# LOOM_-_LV_BOX.net
KiCad netlist of a schematic drawn in Altium Designer
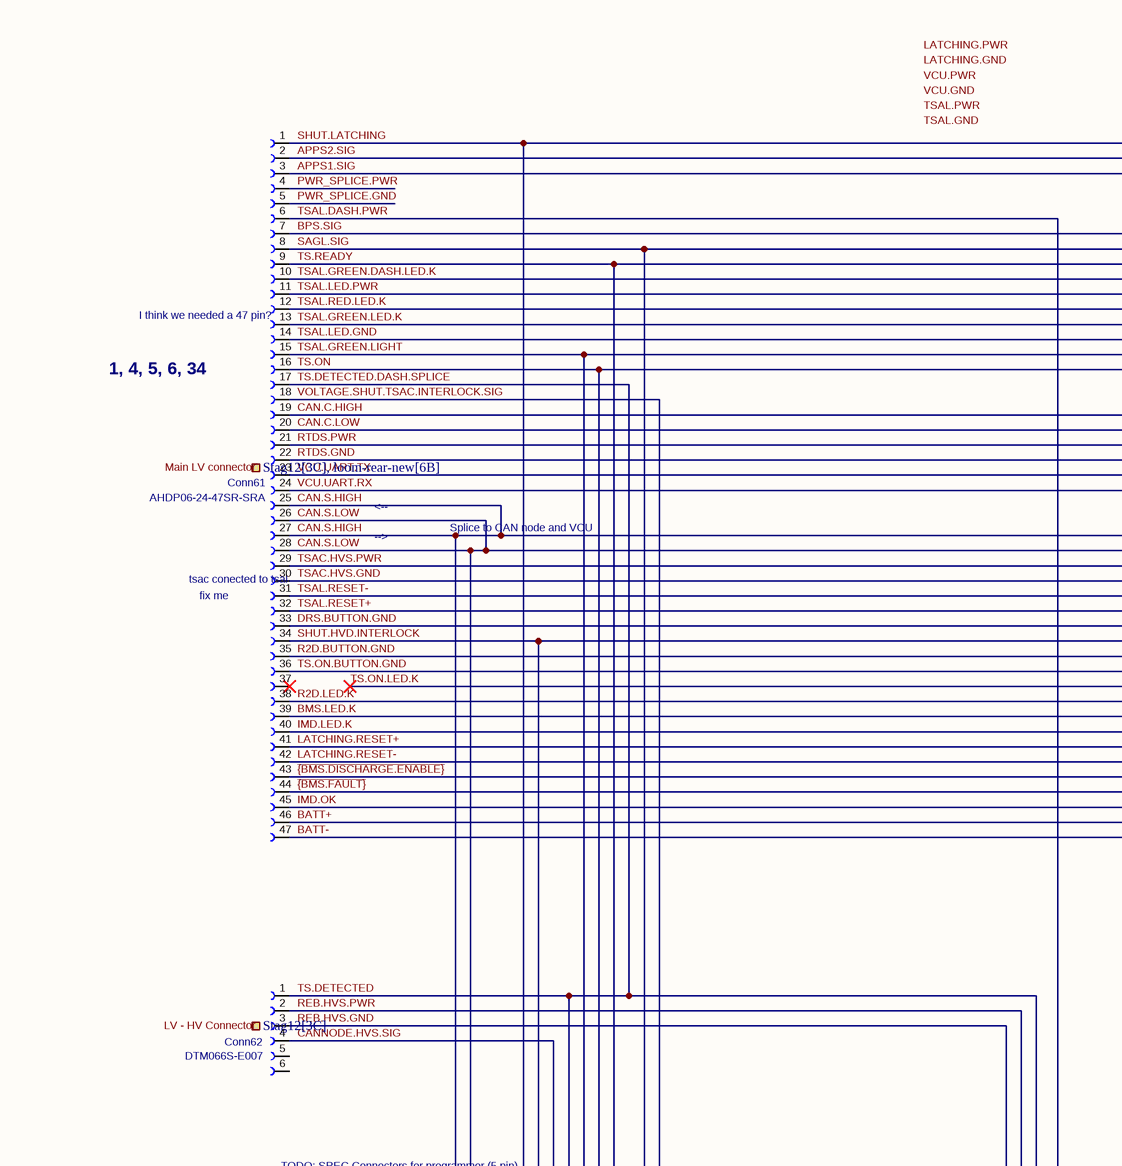
[diagram p0: LOOM - LV BOX.SchDoc, top left]
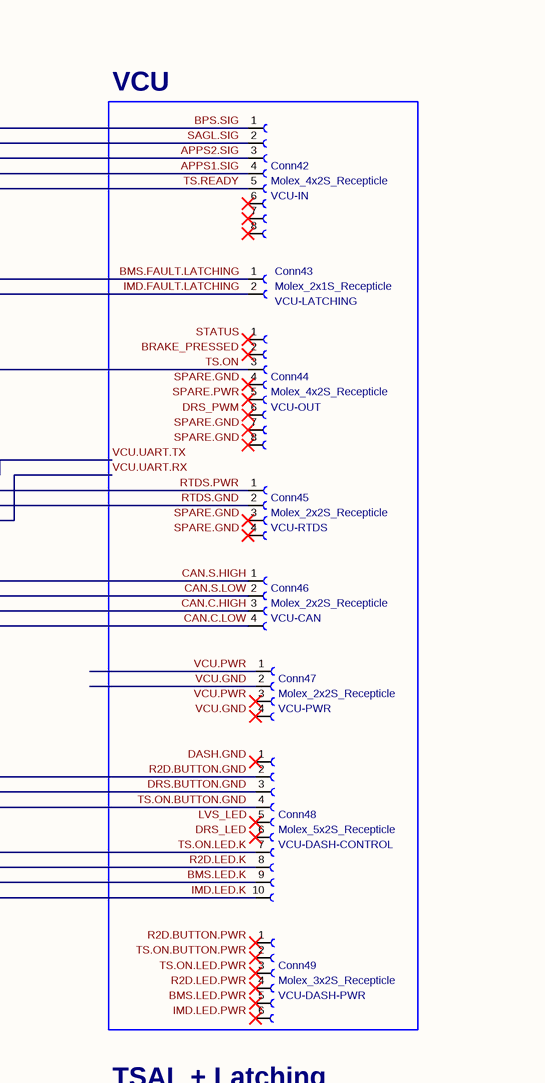
[diagram p1: LOOM - LV BOX.SchDoc, top right]
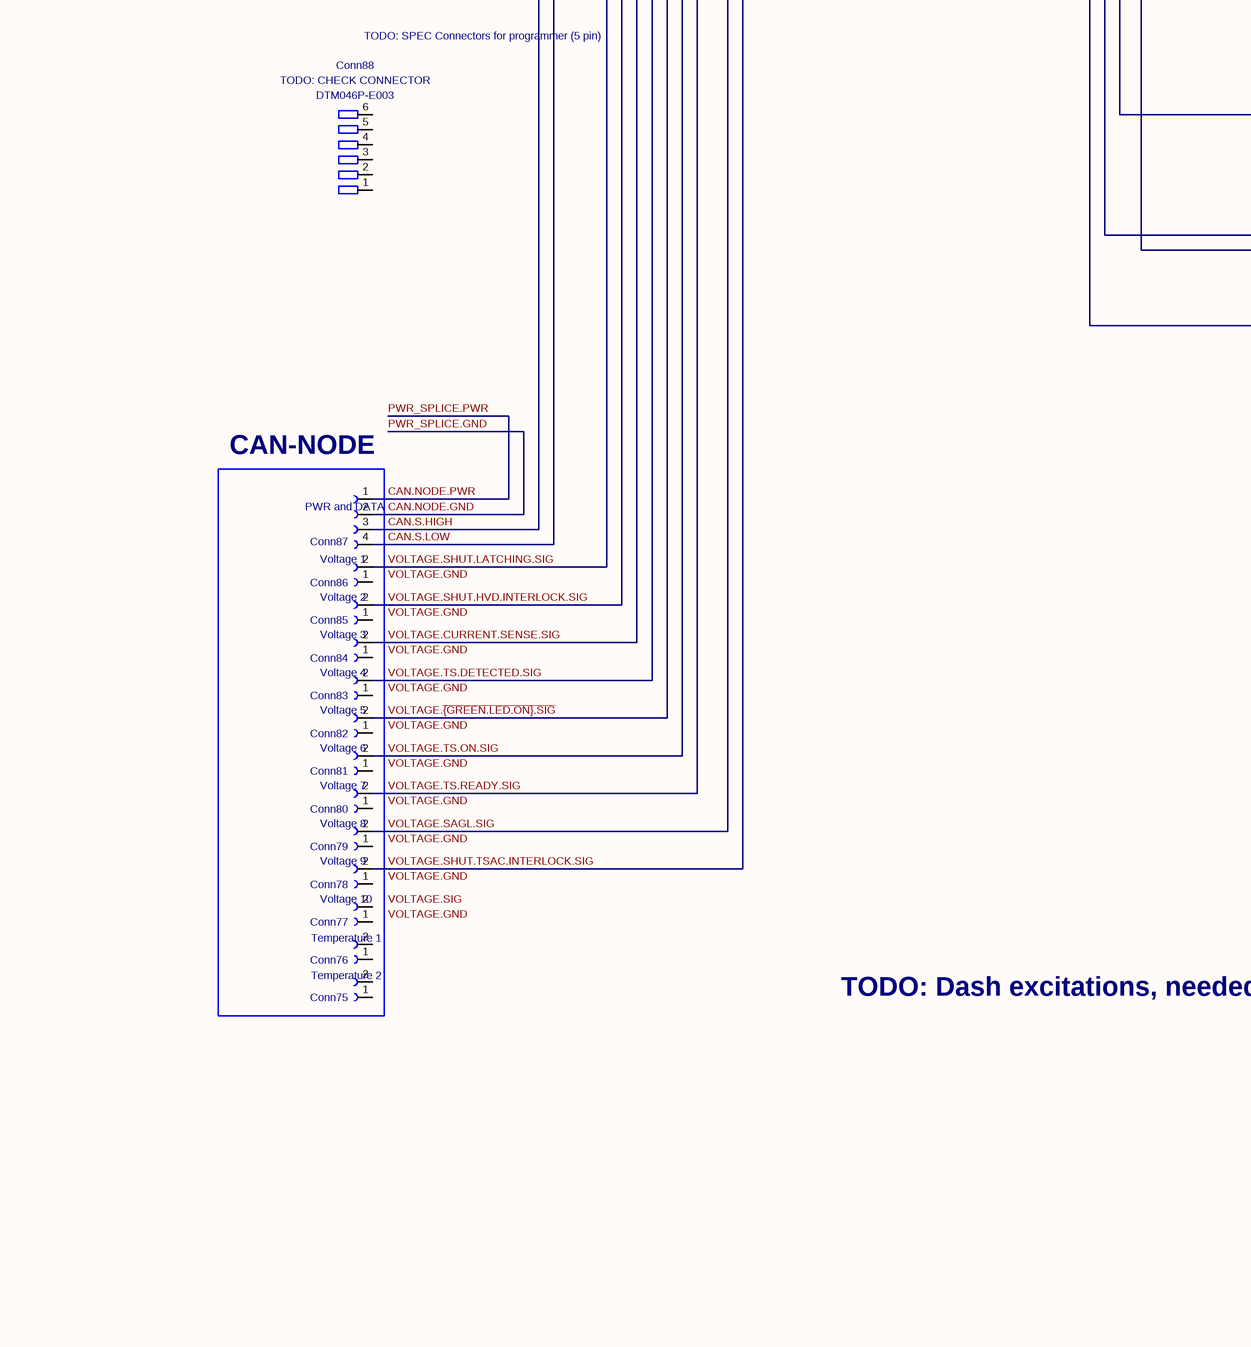
[diagram p2: LOOM - LV BOX.SchDoc, bottom left]
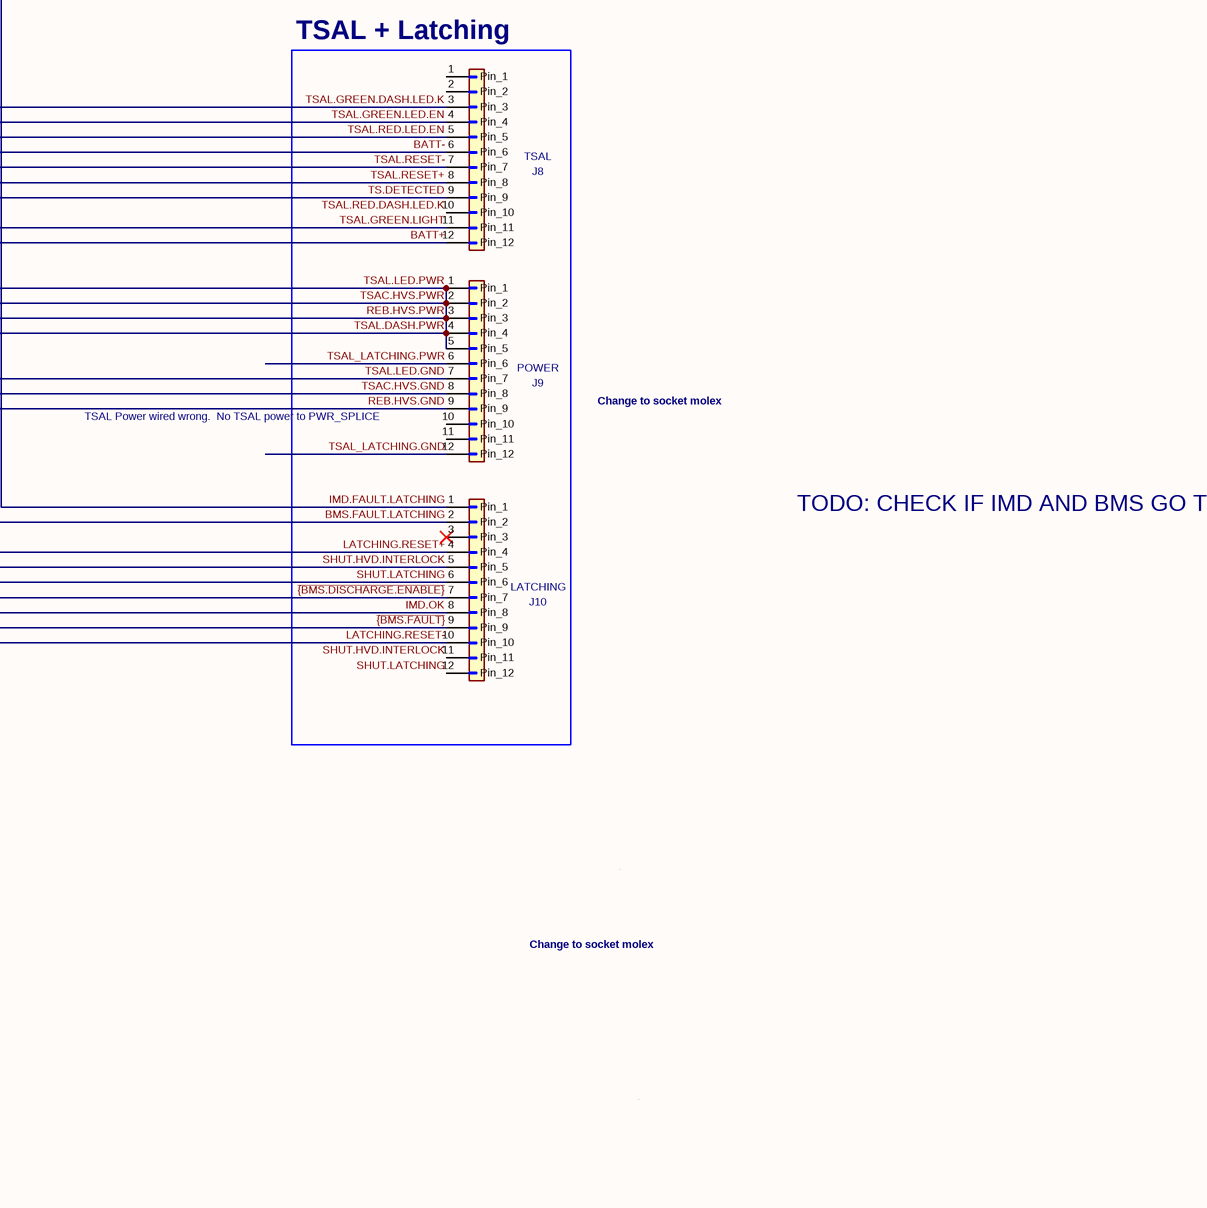
[diagram p3: LOOM - LV BOX.SchDoc, bottom right]

(export (version "E")
  (design (tool "Eeschema 10.0.6"))
  (components
    (comp (ref "Conn42")
      (value "Molex_4x2S_Recepticle")
      (fields (field (name "CONN NAME") "VCU-IN"))
      (libsource (lib "Connectors_SUFST") (part "Molex_4x2S_Recepticle"))
    )
    (comp (ref "Conn43")
      (value "Molex_2x1S_Recepticle")
      (fields (field (name "CONN NAME") "VCU-LATCHING"))
      (libsource (lib "Connectors_SUFST") (part "Molex_2x1S_Recepticle"))
    )
    (comp (ref "Conn44")
      (value "Molex_4x2S_Recepticle")
      (fields (field (name "CONN NAME") "VCU-OUT"))
      (libsource (lib "Connectors_SUFST") (part "Molex_4x2S_Recepticle"))
    )
    (comp (ref "Conn45")
      (value "Molex_2x2S_Recepticle")
      (fields (field (name "CONN NAME") "VCU-RTDS"))
      (libsource (lib "Connectors_SUFST") (part "Molex_2x2S_Recepticle"))
    )
    (comp (ref "Conn46")
      (value "Molex_2x2S_Recepticle")
      (fields (field (name "CONN NAME") "VCU-CAN"))
      (libsource (lib "Connectors_SUFST") (part "Molex_2x2S_Recepticle"))
    )
    (comp (ref "Conn47")
      (value "Molex_2x2S_Recepticle")
      (fields (field (name "CONN NAME") "VCU-PWR"))
      (libsource (lib "Connectors_SUFST") (part "Molex_2x2S_Recepticle"))
    )
    (comp (ref "Conn48")
      (value "Molex_5x2S_Recepticle")
      (fields (field (name "CONN NAME") "VCU-DASH-CONTROL"))
      (libsource (lib "Connectors_SUFST") (part "Molex_5x2S_Recepticle"))
    )
    (comp (ref "Conn49")
      (value "Molex_3x2S_Recepticle")
      (fields (field (name "CONN NAME") "VCU-DASH-PWR"))
      (libsource (lib "Connectors_SUFST") (part "Molex_3x2S_Recepticle"))
    )
    (comp (ref "Conn61")
      (value "AMPHENOL-47P-Recepticle")
      (fields (field (name "P/N") "AHDP06-24-47SR-SRA"))
      (libsource (lib "Connectors_SUFST") (part "AMPHENOL-47P-Recepticle"))
    )
    (comp (ref "Conn62")
      (value "Deutsch_DTM_12S_Pin")
      (fields (field (name "P/N") "DTM066S-E007"))
      (libsource (lib "Connectors_SUFST") (part "Deutsch_DTM_6S_Pin"))
    )
    (comp (ref "Conn75")
      (value "Molex_2x1S_Recepticle")
      (libsource (lib "Connectors_SUFST") (part "Molex_2x1S_Recepticle"))
    )
    (comp (ref "Conn76")
      (value "Molex_2x1S_Recepticle")
      (libsource (lib "Connectors_SUFST") (part "Molex_2x1S_Recepticle"))
    )
    (comp (ref "Conn77")
      (value "Molex_2x1S_Recepticle")
      (libsource (lib "Connectors_SUFST") (part "Molex_2x1S_Recepticle"))
    )
    (comp (ref "Conn78")
      (value "Molex_2x1S_Recepticle")
      (libsource (lib "Connectors_SUFST") (part "Molex_2x1S_Recepticle"))
    )
    (comp (ref "Conn79")
      (value "Molex_2x1S_Recepticle")
      (libsource (lib "Connectors_SUFST") (part "Molex_2x1S_Recepticle"))
    )
    (comp (ref "Conn80")
      (value "Molex_2x1S_Recepticle")
      (libsource (lib "Connectors_SUFST") (part "Molex_2x1S_Recepticle"))
    )
    (comp (ref "Conn81")
      (value "Molex_2x1S_Recepticle")
      (libsource (lib "Connectors_SUFST") (part "Molex_2x1S_Recepticle"))
    )
    (comp (ref "Conn82")
      (value "Molex_2x1S_Recepticle")
      (libsource (lib "Connectors_SUFST") (part "Molex_2x1S_Recepticle"))
    )
    (comp (ref "Conn83")
      (value "Molex_2x1S_Recepticle")
      (libsource (lib "Connectors_SUFST") (part "Molex_2x1S_Recepticle"))
    )
    (comp (ref "Conn84")
      (value "Molex_2x1S_Recepticle")
      (libsource (lib "Connectors_SUFST") (part "Molex_2x1S_Recepticle"))
    )
    (comp (ref "Conn85")
      (value "Molex_2x1S_Recepticle")
      (libsource (lib "Connectors_SUFST") (part "Molex_2x1S_Recepticle"))
    )
    (comp (ref "Conn86")
      (value "Molex_2x1S_Recepticle")
      (libsource (lib "Connectors_SUFST") (part "Molex_2x1S_Recepticle"))
    )
    (comp (ref "Conn87")
      (value "Molex_4x1S_Recepticle")
      (libsource (lib "Connectors_SUFST") (part "Molex_4x1S_Recepticle"))
    )
    (comp (ref "Conn88")
      (value "TODO: CHECK CONNECTOR")
      (fields (field (name "P/N") "DTM046P-E003"))
      (libsource (lib "Connectors_SUFST") (part "Deutsch_DTM_6P_Pin"))
    )
    (comp (ref "J8")
      (value "TSAL")
      (footprint "Molex_Micro-Fit_3.0_43045-1200_2x06_P3.00mm_Horizontal")
      (libsource (lib "Connector_Generic") (part "Conn_01x12"))
    )
    (comp (ref "J9")
      (value "POWER")
      (footprint "Molex_Micro-Fit_3.0_43045-1200_2x06_P3.00mm_Horizontal")
      (libsource (lib "Connector_Generic") (part "Conn_01x12"))
    )
    (comp (ref "J10")
      (value "LATCHING")
      (footprint "Molex_Micro-Fit_3.0_43045-1200_2x06_P3.00mm_Horizontal")
      (libsource (lib "Connector_Generic") (part "Conn_01x12"))
    )
  )
  (nets
    (net (code "1") (name "/APPS1.SIG") (class "Default")
      (node (ref "Conn42") (pin "4") (pinfunction "4_4") (pintype "passive"))
      (node (ref "Conn61") (pin "3") (pinfunction "3_3") (pintype "passive"))
    )
    (net (code "2") (name "/APPS2.SIG") (class "Default")
      (node (ref "Conn42") (pin "3") (pinfunction "3_3") (pintype "passive"))
      (node (ref "Conn61") (pin "2") (pinfunction "2_2") (pintype "passive"))
    )
    (net (code "3") (name "/BATT+") (class "Default")
      (node (ref "Conn61") (pin "46") (pinfunction "46_46") (pintype "passive"))
      (node (ref "J8") (pin "12") (pinfunction "Pin_12_12") (pintype "passive"))
    )
    (net (code "4") (name "/BATT-") (class "Default")
      (node (ref "Conn61") (pin "47") (pinfunction "47_47") (pintype "passive"))
      (node (ref "J8") (pin "6") (pinfunction "Pin_6_6") (pintype "passive"))
    )
    (net (code "5") (name "/BMS.FAULT.LATCHING") (class "Default")
      (node (ref "Conn43") (pin "1") (pinfunction "1_1") (pintype "passive"))
      (node (ref "J10") (pin "2") (pinfunction "Pin_2_2") (pintype "passive"))
    )
    (net (code "6") (name "/BMS.LED.K") (class "Default")
      (node (ref "Conn48") (pin "9") (pinfunction "9_9") (pintype "passive"))
      (node (ref "Conn61") (pin "39") (pinfunction "39_39") (pintype "passive"))
    )
    (net (code "8") (name "/BPS.SIG") (class "Default")
      (node (ref "Conn42") (pin "1") (pinfunction "1_1") (pintype "passive"))
      (node (ref "Conn61") (pin "7") (pinfunction "7_7") (pintype "passive"))
    )
    (net (code "10") (name "/CAN.C.HIGH") (class "Default")
      (node (ref "Conn46") (pin "3") (pinfunction "3_3") (pintype "passive"))
      (node (ref "Conn61") (pin "19") (pinfunction "19_19") (pintype "passive"))
    )
    (net (code "11") (name "/CAN.C.LOW") (class "Default")
      (node (ref "Conn46") (pin "4") (pinfunction "4_4") (pintype "passive"))
      (node (ref "Conn61") (pin "20") (pinfunction "20_20") (pintype "passive"))
    )
    (net (code "12") (name "/CAN.NODE.GND") (class "Default")
      (node (ref "Conn61") (pin "5") (pinfunction "5_5") (pintype "passive"))
      (node (ref "Conn87") (pin "2") (pinfunction "2_2") (pintype "passive"))
    )
    (net (code "13") (name "/CAN.NODE.PWR") (class "Default")
      (node (ref "Conn61") (pin "4") (pinfunction "4_4") (pintype "passive"))
      (node (ref "Conn87") (pin "1") (pinfunction "1_1") (pintype "passive"))
    )
    (net (code "14") (name "/CAN.S.HIGH") (class "Default")
      (node (ref "Conn46") (pin "1") (pinfunction "1_1") (pintype "passive"))
      (node (ref "Conn61") (pin "25") (pinfunction "25_25") (pintype "passive"))
      (node (ref "Conn61") (pin "27") (pinfunction "27_27") (pintype "passive"))
      (node (ref "Conn87") (pin "3") (pinfunction "3_3") (pintype "passive"))
    )
    (net (code "15") (name "/CAN.S.LOW") (class "Default")
      (node (ref "Conn46") (pin "2") (pinfunction "2_2") (pintype "passive"))
      (node (ref "Conn61") (pin "26") (pinfunction "26_26") (pintype "passive"))
      (node (ref "Conn61") (pin "28") (pinfunction "28_28") (pintype "passive"))
      (node (ref "Conn87") (pin "4") (pinfunction "4_4") (pintype "passive"))
    )
    (net (code "16") (name "/CANNODE.HVS.SIG") (class "Default")
      (node (ref "Conn62") (pin "4") (pinfunction "4_4") (pintype "passive"))
      (node (ref "Conn84") (pin "2") (pinfunction "2_2") (pintype "passive"))
    )
    (net (code "18") (name "/DRS.BUTTON.GND") (class "Default")
      (node (ref "Conn48") (pin "3") (pinfunction "3_3") (pintype "passive"))
      (node (ref "Conn61") (pin "33") (pinfunction "33_33") (pintype "passive"))
    )
    (net (code "21") (name "/IMD.FAULT.LATCHING") (class "Default")
      (node (ref "Conn43") (pin "2") (pinfunction "2_2") (pintype "passive"))
      (node (ref "J10") (pin "1") (pinfunction "Pin_1_1") (pintype "passive"))
    )
    (net (code "22") (name "/IMD.LED.K") (class "Default")
      (node (ref "Conn48") (pin "10") (pinfunction "10_10") (pintype "passive"))
      (node (ref "Conn61") (pin "40") (pinfunction "40_40") (pintype "passive"))
    )
    (net (code "24") (name "/IMD.OK") (class "Default")
      (node (ref "Conn61") (pin "45") (pinfunction "45_45") (pintype "passive"))
      (node (ref "J10") (pin "8") (pinfunction "Pin_8_8") (pintype "passive"))
    )
    (net (code "27") (name "/LATCHING.RESET+") (class "Default")
      (node (ref "Conn61") (pin "41") (pinfunction "41_41") (pintype "passive"))
      (node (ref "J10") (pin "4") (pinfunction "Pin_4_4") (pintype "passive"))
    )
    (net (code "28") (name "/LATCHING.RESET-") (class "Default")
      (node (ref "Conn61") (pin "42") (pinfunction "42_42") (pintype "passive"))
      (node (ref "J10") (pin "10") (pinfunction "Pin_10_10") (pintype "passive"))
    )
    (net (code "32") (name "/R2D.BUTTON.GND") (class "Default")
      (node (ref "Conn48") (pin "2") (pinfunction "2_2") (pintype "passive"))
      (node (ref "Conn61") (pin "35") (pinfunction "35_35") (pintype "passive"))
    )
    (net (code "34") (name "/R2D.LED.K") (class "Default")
      (node (ref "Conn48") (pin "8") (pinfunction "8_8") (pintype "passive"))
      (node (ref "Conn61") (pin "38") (pinfunction "38_38") (pintype "passive"))
    )
    (net (code "36") (name "/REB.HVS.GND") (class "Default")
      (node (ref "Conn62") (pin "3") (pinfunction "3_3") (pintype "passive"))
      (node (ref "J9") (pin "9") (pinfunction "Pin_9_9") (pintype "passive"))
    )
    (net (code "37") (name "/REB.HVS.PWR") (class "Default")
      (node (ref "Conn61") (pin "11") (pinfunction "11_11") (pintype "passive"))
      (node (ref "Conn61") (pin "29") (pinfunction "29_29") (pintype "passive"))
      (node (ref "Conn61") (pin "6") (pinfunction "6_6") (pintype "passive"))
      (node (ref "Conn62") (pin "2") (pinfunction "2_2") (pintype "passive"))
      (node (ref "J9") (pin "1") (pinfunction "Pin_1_1") (pintype "passive"))
      (node (ref "J9") (pin "2") (pinfunction "Pin_2_2") (pintype "passive"))
      (node (ref "J9") (pin "3") (pinfunction "Pin_3_3") (pintype "passive"))
      (node (ref "J9") (pin "4") (pinfunction "Pin_4_4") (pintype "passive"))
      (node (ref "J9") (pin "5") (pinfunction "Pin_5_5") (pintype "passive"))
    )
    (net (code "38") (name "/RTDS.GND") (class "Default")
      (node (ref "Conn45") (pin "2") (pinfunction "2_2") (pintype "passive"))
      (node (ref "Conn61") (pin "22") (pinfunction "22_22") (pintype "passive"))
    )
    (net (code "39") (name "/RTDS.PWR") (class "Default")
      (node (ref "Conn45") (pin "1") (pinfunction "1_1") (pintype "passive"))
      (node (ref "Conn61") (pin "21") (pinfunction "21_21") (pintype "passive"))
    )
    (net (code "40") (name "/SAGL.SIG") (class "Default")
      (node (ref "Conn42") (pin "2") (pinfunction "2_2") (pintype "passive"))
      (node (ref "Conn61") (pin "8") (pinfunction "8_8") (pintype "passive"))
      (node (ref "Conn79") (pin "2") (pinfunction "2_2") (pintype "passive"))
    )
    (net (code "41") (name "/SHUT.HVD.INTERLOCK") (class "Default")
      (node (ref "Conn61") (pin "34") (pinfunction "34_34") (pintype "passive"))
      (node (ref "Conn85") (pin "2") (pinfunction "2_2") (pintype "passive"))
      (node (ref "J10") (pin "11") (pinfunction "Pin_11_11") (pintype "passive"))
      (node (ref "J10") (pin "5") (pinfunction "Pin_5_5") (pintype "passive"))
    )
    (net (code "42") (name "/SHUT.LATCHING") (class "Default")
      (node (ref "Conn61") (pin "1") (pinfunction "1_1") (pintype "passive"))
      (node (ref "Conn86") (pin "2") (pinfunction "2_2") (pintype "passive"))
      (node (ref "J10") (pin "12") (pinfunction "Pin_12_12") (pintype "passive"))
      (node (ref "J10") (pin "6") (pinfunction "Pin_6_6") (pintype "passive"))
    )
    (net (code "46") (name "/TS.DETECTED") (class "Default")
      (node (ref "Conn61") (pin "17") (pinfunction "17_17") (pintype "passive"))
      (node (ref "Conn62") (pin "1") (pinfunction "1_1") (pintype "passive"))
      (node (ref "Conn83") (pin "2") (pinfunction "2_2") (pintype "passive"))
      (node (ref "J8") (pin "9") (pinfunction "Pin_9_9") (pintype "passive"))
    )
    (net (code "47") (name "/TS.ON") (class "Default")
      (node (ref "Conn44") (pin "3") (pinfunction "3_3") (pintype "passive"))
      (node (ref "Conn61") (pin "16") (pinfunction "16_16") (pintype "passive"))
      (node (ref "Conn81") (pin "2") (pinfunction "2_2") (pintype "passive"))
    )
    (net (code "48") (name "/TS.ON.BUTTON.GND") (class "Default")
      (node (ref "Conn48") (pin "4") (pinfunction "4_4") (pintype "passive"))
      (node (ref "Conn61") (pin "36") (pinfunction "36_36") (pintype "passive"))
    )
    (net (code "50") (name "/TS.ON.LED.K") (class "Default")
      (node (ref "Conn48") (pin "7") (pinfunction "7_7") (pintype "passive+no_connect"))
    )
    (net (code "52") (name "/TS.READY") (class "Default")
      (node (ref "Conn42") (pin "5") (pinfunction "5_5") (pintype "passive"))
      (node (ref "Conn61") (pin "9") (pinfunction "9_9") (pintype "passive"))
      (node (ref "Conn80") (pin "2") (pinfunction "2_2") (pintype "passive"))
    )
    (net (code "53") (name "/TSAC.HVS.GND") (class "Default")
      (node (ref "Conn61") (pin "30") (pinfunction "30_30") (pintype "passive"))
      (node (ref "J9") (pin "8") (pinfunction "Pin_8_8") (pintype "passive"))
    )
    (net (code "55") (name "/TSAL.GREEN.DASH.LED.K") (class "Default")
      (node (ref "Conn61") (pin "10") (pinfunction "10_10") (pintype "passive"))
      (node (ref "J8") (pin "3") (pinfunction "Pin_3_3") (pintype "passive"))
    )
    (net (code "56") (name "/TSAL.GREEN.LED.EN") (class "Default")
      (node (ref "Conn61") (pin "13") (pinfunction "13_13") (pintype "passive"))
      (node (ref "J8") (pin "4") (pinfunction "Pin_4_4") (pintype "passive"))
    )
    (net (code "57") (name "/TSAL.GREEN.LIGHT") (class "Default")
      (node (ref "Conn61") (pin "15") (pinfunction "15_15") (pintype "passive"))
      (node (ref "Conn82") (pin "2") (pinfunction "2_2") (pintype "passive"))
      (node (ref "J8") (pin "11") (pinfunction "Pin_11_11") (pintype "passive"))
    )
    (net (code "58") (name "/TSAL.LED.GND") (class "Default")
      (node (ref "Conn61") (pin "14") (pinfunction "14_14") (pintype "passive"))
      (node (ref "J9") (pin "7") (pinfunction "Pin_7_7") (pintype "passive"))
    )
    (net (code "60") (name "/TSAL.RED.DASH.LED.K") (class "Default")
      (node (ref "J8") (pin "10") (pinfunction "Pin_10_10") (pintype "passive"))
    )
    (net (code "61") (name "/TSAL.RED.LED.EN") (class "Default")
      (node (ref "Conn61") (pin "12") (pinfunction "12_12") (pintype "passive"))
      (node (ref "J8") (pin "5") (pinfunction "Pin_5_5") (pintype "passive"))
    )
    (net (code "62") (name "/TSAL.RESET+") (class "Default")
      (node (ref "Conn61") (pin "32") (pinfunction "32_32") (pintype "passive"))
      (node (ref "J8") (pin "8") (pinfunction "Pin_8_8") (pintype "passive"))
    )
    (net (code "63") (name "/TSAL.RESET-") (class "Default")
      (node (ref "Conn61") (pin "31") (pinfunction "31_31") (pintype "passive"))
      (node (ref "J8") (pin "7") (pinfunction "Pin_7_7") (pintype "passive"))
    )
    (net (code "64") (name "/TSAL_LATCHING.GND") (class "Default")
      (node (ref "J9") (pin "12") (pinfunction "Pin_12_12") (pintype "passive"))
    )
    (net (code "65") (name "/TSAL_LATCHING.PWR") (class "Default")
      (node (ref "J9") (pin "6") (pinfunction "Pin_6_6") (pintype "passive"))
    )
    (net (code "66") (name "/VCU.GND") (class "Default")
      (node (ref "Conn47") (pin "2") (pinfunction "2_2") (pintype "passive"))
    )
    (net (code "67") (name "/VCU.PWR") (class "Default")
      (node (ref "Conn47") (pin "1") (pinfunction "1_1") (pintype "passive"))
    )
    (net (code "68") (name "/VCU.UART.RX") (class "Default")
      (node (ref "Conn61") (pin "24") (pinfunction "24_24") (pintype "passive"))
    )
    (net (code "69") (name "/VCU.UART.TX") (class "Default")
      (node (ref "Conn61") (pin "23") (pinfunction "23_23") (pintype "passive"))
    )
    (net (code "71") (name "/VOLTAGE.SHUT.TSAC.INTERLOCK.SIG") (class "Default")
      (node (ref "Conn61") (pin "18") (pinfunction "18_18") (pintype "passive"))
      (node (ref "Conn78") (pin "2") (pinfunction "2_2") (pintype "passive"))
    )
    (net (code "73") (name "/~{{BMS.DISCHARGE.ENABLE}}") (class "Default")
      (node (ref "Conn61") (pin "43") (pinfunction "43_43") (pintype "passive"))
      (node (ref "J10") (pin "7") (pinfunction "Pin_7_7") (pintype "passive"))
    )
    (net (code "74") (name "/~{{BMS.FAULT}}") (class "Default")
      (node (ref "Conn61") (pin "44") (pinfunction "44_44") (pintype "passive"))
      (node (ref "J10") (pin "9") (pinfunction "Pin_9_9") (pintype "passive"))
    )
    (net (code "75") (name "unconnected-(Conn42-Pad6)") (class "Default")
      (node (ref "Conn42") (pin "6") (pinfunction "6_6") (pintype "passive+no_connect"))
    )
    (net (code "76") (name "unconnected-(Conn42-Pad7)") (class "Default")
      (node (ref "Conn42") (pin "7") (pinfunction "7_7") (pintype "passive+no_connect"))
    )
    (net (code "77") (name "unconnected-(Conn42-Pad8)") (class "Default")
      (node (ref "Conn42") (pin "8") (pinfunction "8_8") (pintype "passive+no_connect"))
    )
    (net (code "78") (name "unconnected-(Conn44-Pad1)") (class "Default")
      (node (ref "Conn44") (pin "1") (pinfunction "1_1") (pintype "passive+no_connect"))
    )
    (net (code "79") (name "unconnected-(Conn44-Pad2)") (class "Default")
      (node (ref "Conn44") (pin "2") (pinfunction "2_2") (pintype "passive+no_connect"))
    )
    (net (code "80") (name "unconnected-(Conn44-Pad4)") (class "Default")
      (node (ref "Conn44") (pin "4") (pinfunction "4_4") (pintype "passive+no_connect"))
    )
    (net (code "81") (name "unconnected-(Conn44-Pad5)") (class "Default")
      (node (ref "Conn44") (pin "5") (pinfunction "5_5") (pintype "passive+no_connect"))
    )
    (net (code "82") (name "unconnected-(Conn44-Pad6)") (class "Default")
      (node (ref "Conn44") (pin "6") (pinfunction "6_6") (pintype "passive+no_connect"))
    )
    (net (code "83") (name "unconnected-(Conn44-Pad7)") (class "Default")
      (node (ref "Conn44") (pin "7") (pinfunction "7_7") (pintype "passive+no_connect"))
    )
    (net (code "84") (name "unconnected-(Conn44-Pad8)") (class "Default")
      (node (ref "Conn44") (pin "8") (pinfunction "8_8") (pintype "passive+no_connect"))
    )
    (net (code "85") (name "unconnected-(Conn45-Pad3)") (class "Default")
      (node (ref "Conn45") (pin "3") (pinfunction "3_3") (pintype "passive+no_connect"))
    )
    (net (code "86") (name "unconnected-(Conn45-Pad4)") (class "Default")
      (node (ref "Conn45") (pin "4") (pinfunction "4_4") (pintype "passive+no_connect"))
    )
    (net (code "87") (name "unconnected-(Conn47-Pad3)") (class "Default")
      (node (ref "Conn47") (pin "3") (pinfunction "3_3") (pintype "passive+no_connect"))
    )
    (net (code "88") (name "unconnected-(Conn47-Pad4)") (class "Default")
      (node (ref "Conn47") (pin "4") (pinfunction "4_4") (pintype "passive+no_connect"))
    )
    (net (code "89") (name "unconnected-(Conn48-Pad1)") (class "Default")
      (node (ref "Conn48") (pin "1") (pinfunction "1_1") (pintype "passive+no_connect"))
    )
    (net (code "90") (name "unconnected-(Conn48-Pad5)") (class "Default")
      (node (ref "Conn48") (pin "5") (pinfunction "5_5") (pintype "passive+no_connect"))
    )
    (net (code "91") (name "unconnected-(Conn48-Pad6)") (class "Default")
      (node (ref "Conn48") (pin "6") (pinfunction "6_6") (pintype "passive+no_connect"))
    )
    (net (code "92") (name "unconnected-(Conn49-Pad1)") (class "Default")
      (node (ref "Conn49") (pin "1") (pinfunction "1_1") (pintype "passive+no_connect"))
    )
    (net (code "93") (name "unconnected-(Conn49-Pad2)") (class "Default")
      (node (ref "Conn49") (pin "2") (pinfunction "2_2") (pintype "passive+no_connect"))
    )
    (net (code "94") (name "unconnected-(Conn49-Pad3)") (class "Default")
      (node (ref "Conn49") (pin "3") (pinfunction "3_3") (pintype "passive+no_connect"))
    )
    (net (code "95") (name "unconnected-(Conn49-Pad4)") (class "Default")
      (node (ref "Conn49") (pin "4") (pinfunction "4_4") (pintype "passive+no_connect"))
    )
    (net (code "96") (name "unconnected-(Conn49-Pad5)") (class "Default")
      (node (ref "Conn49") (pin "5") (pinfunction "5_5") (pintype "passive+no_connect"))
    )
    (net (code "97") (name "unconnected-(Conn49-Pad6)") (class "Default")
      (node (ref "Conn49") (pin "6") (pinfunction "6_6") (pintype "passive+no_connect"))
    )
    (net (code "98") (name "unconnected-(Conn61-Pad37)") (class "Default")
      (node (ref "Conn61") (pin "37") (pinfunction "37_37") (pintype "passive+no_connect"))
    )
    (net (code "99") (name "unconnected-(Conn62-Pad5)") (class "Default")
      (node (ref "Conn62") (pin "5") (pinfunction "5_5") (pintype "passive"))
    )
    (net (code "100") (name "unconnected-(Conn62-Pad6)") (class "Default")
      (node (ref "Conn62") (pin "6") (pinfunction "6_6") (pintype "passive"))
    )
    (net (code "101") (name "unconnected-(Conn75-Pad1)") (class "Default")
      (node (ref "Conn75") (pin "1") (pinfunction "1_1") (pintype "passive"))
    )
    (net (code "102") (name "unconnected-(Conn75-Pad2)") (class "Default")
      (node (ref "Conn75") (pin "2") (pinfunction "2_2") (pintype "passive"))
    )
    (net (code "103") (name "unconnected-(Conn76-Pad1)") (class "Default")
      (node (ref "Conn76") (pin "1") (pinfunction "1_1") (pintype "passive"))
    )
    (net (code "104") (name "unconnected-(Conn76-Pad2)") (class "Default")
      (node (ref "Conn76") (pin "2") (pinfunction "2_2") (pintype "passive"))
    )
    (net (code "105") (name "unconnected-(Conn77-Pad1)") (class "Default")
      (node (ref "Conn77") (pin "1") (pinfunction "1_1") (pintype "passive"))
    )
    (net (code "106") (name "unconnected-(Conn77-Pad2)") (class "Default")
      (node (ref "Conn77") (pin "2") (pinfunction "2_2") (pintype "passive"))
    )
    (net (code "107") (name "unconnected-(Conn78-Pad1)") (class "Default")
      (node (ref "Conn78") (pin "1") (pinfunction "1_1") (pintype "passive"))
    )
    (net (code "108") (name "unconnected-(Conn79-Pad1)") (class "Default")
      (node (ref "Conn79") (pin "1") (pinfunction "1_1") (pintype "passive"))
    )
    (net (code "109") (name "unconnected-(Conn80-Pad1)") (class "Default")
      (node (ref "Conn80") (pin "1") (pinfunction "1_1") (pintype "passive"))
    )
    (net (code "110") (name "unconnected-(Conn81-Pad1)") (class "Default")
      (node (ref "Conn81") (pin "1") (pinfunction "1_1") (pintype "passive"))
    )
    (net (code "111") (name "unconnected-(Conn82-Pad1)") (class "Default")
      (node (ref "Conn82") (pin "1") (pinfunction "1_1") (pintype "passive"))
    )
    (net (code "112") (name "unconnected-(Conn83-Pad1)") (class "Default")
      (node (ref "Conn83") (pin "1") (pinfunction "1_1") (pintype "passive"))
    )
    (net (code "113") (name "unconnected-(Conn84-Pad1)") (class "Default")
      (node (ref "Conn84") (pin "1") (pinfunction "1_1") (pintype "passive"))
    )
    (net (code "114") (name "unconnected-(Conn85-Pad1)") (class "Default")
      (node (ref "Conn85") (pin "1") (pinfunction "1_1") (pintype "passive"))
    )
    (net (code "115") (name "unconnected-(Conn86-Pad1)") (class "Default")
      (node (ref "Conn86") (pin "1") (pinfunction "1_1") (pintype "passive"))
    )
    (net (code "116") (name "unconnected-(Conn88-Pad1)") (class "Default")
      (node (ref "Conn88") (pin "1") (pinfunction "1_1") (pintype "passive"))
    )
    (net (code "117") (name "unconnected-(Conn88-Pad2)") (class "Default")
      (node (ref "Conn88") (pin "2") (pinfunction "2_2") (pintype "passive"))
    )
    (net (code "118") (name "unconnected-(Conn88-Pad3)") (class "Default")
      (node (ref "Conn88") (pin "3") (pinfunction "3_3") (pintype "passive"))
    )
    (net (code "119") (name "unconnected-(Conn88-Pad4)") (class "Default")
      (node (ref "Conn88") (pin "4") (pinfunction "4_4") (pintype "passive"))
    )
    (net (code "120") (name "unconnected-(Conn88-Pad5)") (class "Default")
      (node (ref "Conn88") (pin "5") (pinfunction "5_5") (pintype "passive"))
    )
    (net (code "121") (name "unconnected-(Conn88-Pad6)") (class "Default")
      (node (ref "Conn88") (pin "6") (pinfunction "6_6") (pintype "passive"))
    )
    (net (code "122") (name "unconnected-(J8-Pin_1-Pad1)") (class "Default")
      (node (ref "J8") (pin "1") (pinfunction "Pin_1_1") (pintype "passive"))
    )
    (net (code "123") (name "unconnected-(J8-Pin_2-Pad2)") (class "Default")
      (node (ref "J8") (pin "2") (pinfunction "Pin_2_2") (pintype "passive"))
    )
    (net (code "124") (name "unconnected-(J9-Pin_10-Pad10)") (class "Default")
      (node (ref "J9") (pin "10") (pinfunction "Pin_10_10") (pintype "passive"))
    )
    (net (code "125") (name "unconnected-(J9-Pin_11-Pad11)") (class "Default")
      (node (ref "J9") (pin "11") (pinfunction "Pin_11_11") (pintype "passive"))
    )
    (net (code "126") (name "unconnected-(J10-Pin_3-Pad3)") (class "Default")
      (node (ref "J10") (pin "3") (pinfunction "Pin_3_3") (pintype "passive+no_connect"))
    )
  )
)
